# Encoder_Unit.net
KiCad netlist of a schematic drawn in Altium Designer
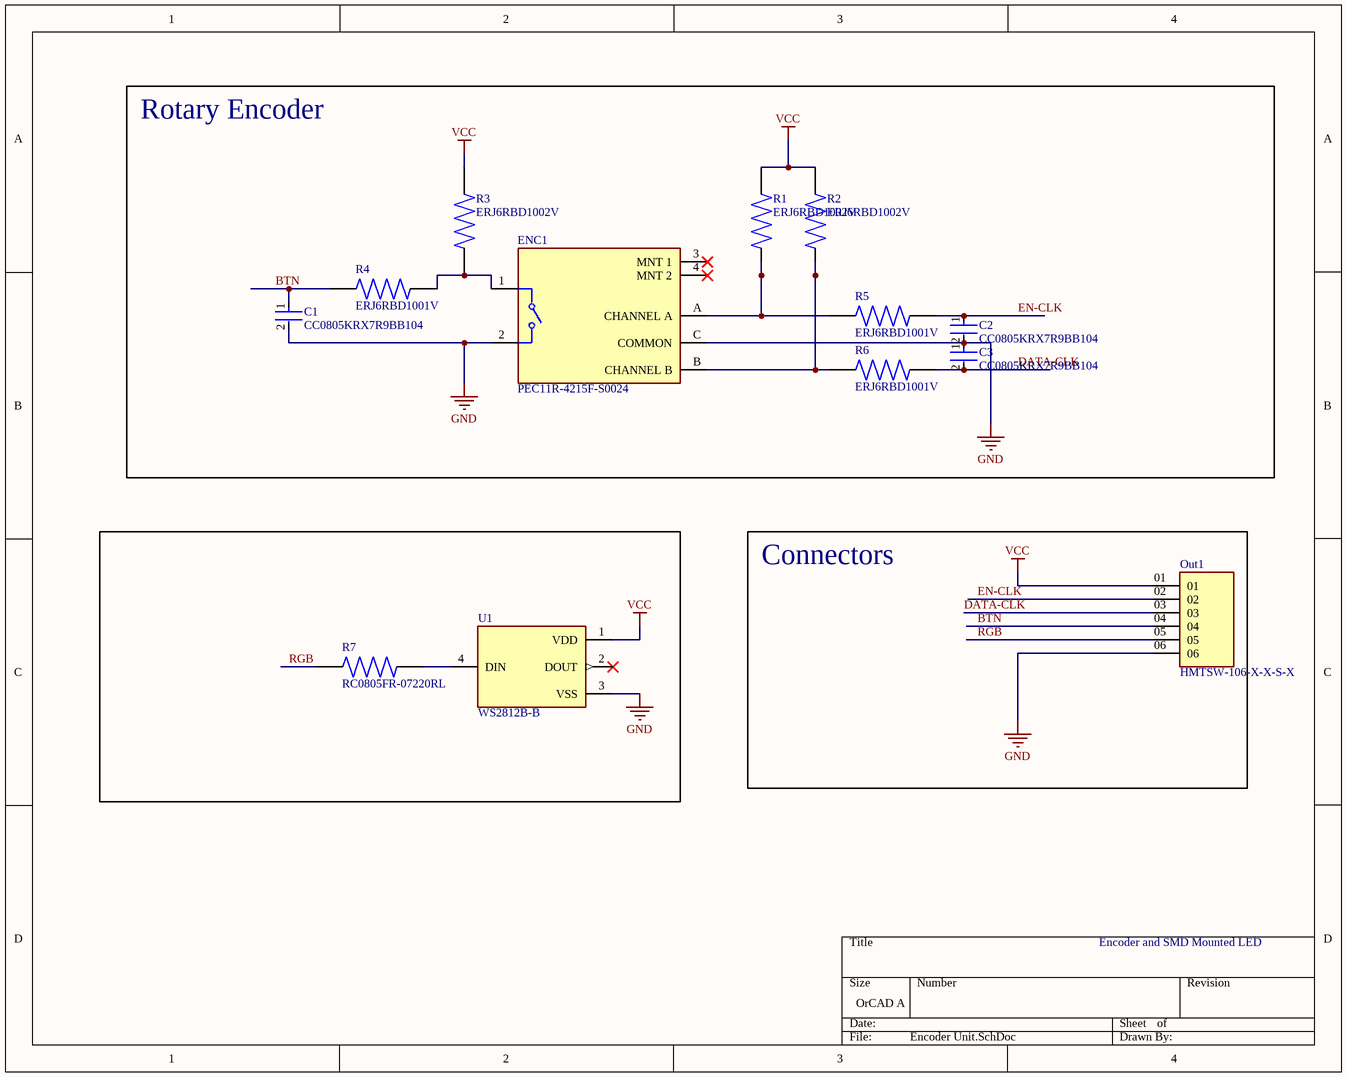
[diagram p0: Encoder Unit.SchDoc]

(export (version "E")
  (design (tool "Eeschema 10.0.6"))
  (components
    (comp (ref "C1")
      (value "CC0805KRX7R9BB104")
      (footprint "FP-CC0805-0_85-IPC_C")
      (description "CAP CER 0.1UF 50V X7R 0805")
      (fields (field (name "TOLERANCE") "0.1") (field (name "MANUFACTURER") "Yageo"))
      (libsource (lib "encoder_lcd_pcb") (part "CMP-2100-03606-3"))
    )
    (comp (ref "C2")
      (value "CC0805KRX7R9BB104")
      (footprint "FP-CC0805-0_85-IPC_C")
      (description "CAP CER 0.1UF 50V X7R 0805")
      (fields (field (name "TOLERANCE") "0.1") (field (name "MANUFACTURER") "Yageo"))
      (libsource (lib "encoder_lcd_pcb") (part "CMP-2100-03606-3"))
    )
    (comp (ref "C3")
      (value "CC0805KRX7R9BB104")
      (footprint "FP-CC0805-0_85-IPC_C")
      (description "CAP CER 0.1UF 50V X7R 0805")
      (fields (field (name "TOLERANCE") "0.1") (field (name "MANUFACTURER") "Yageo"))
      (libsource (lib "encoder_lcd_pcb") (part "CMP-2100-03606-3"))
    )
    (comp (ref "ENC1")
      (value "PEC11R-4215F-S0024")
      (footprint "FP-PEC11R-4215F-S0024-MFG")
      (description "ROTARY ENCODER MECHANICAL 24PPR")
      (fields (field (name "LCSC PART NUMBER") "C143790"))
      (libsource (lib "encoder_lcd_pcb") (part "CMP-1747-00012-2"))
    )
    (comp (ref "Out1")
      (value "HMTSW-106-X-X-S-X")
      (footprint "SAMTEC_HMTSW-106-X-X-S-X")
      (description ".100 High-Temp Variable Post Height Terminal Strip")
      (fields (field (name "MF") "SAMTEC") (field (name "MP") "HMTSW-106-07-T-S-200"))
      (libsource (lib "encoder_lcd_pcb") (part "HMTSW-106-X-X-S-X"))
    )
    (comp (ref "R1")
      (value "ERJ6RBD1002V")
      (footprint "RES_ERJ6RBD1002V")
      (fields (field (name "MF") "Panasonic"))
      (libsource (lib "encoder_lcd_pcb") (part "ERJ6RBD1002V"))
    )
    (comp (ref "R2")
      (value "ERJ6RBD1002V")
      (footprint "RES_ERJ6RBD1002V")
      (fields (field (name "MF") "Panasonic"))
      (libsource (lib "encoder_lcd_pcb") (part "ERJ6RBD1002V"))
    )
    (comp (ref "R3")
      (value "ERJ6RBD1002V")
      (footprint "RES_ERJ6RBD1002V")
      (fields (field (name "MF") "Panasonic"))
      (libsource (lib "encoder_lcd_pcb") (part "ERJ6RBD1002V"))
    )
    (comp (ref "R4")
      (value "ERJ6RBD1001V")
      (footprint "RES_ERJ6RBD1001V")
      (fields (field (name "MF") "Panasonic"))
      (libsource (lib "encoder_lcd_pcb") (part "ERJ6RBD1001V"))
    )
    (comp (ref "R5")
      (value "ERJ6RBD1001V")
      (footprint "RES_ERJ6RBD1001V")
      (fields (field (name "MF") "Panasonic"))
      (libsource (lib "encoder_lcd_pcb") (part "ERJ6RBD1001V"))
    )
    (comp (ref "R6")
      (value "ERJ6RBD1001V")
      (footprint "RES_ERJ6RBD1001V")
      (fields (field (name "MF") "Panasonic"))
      (libsource (lib "encoder_lcd_pcb") (part "ERJ6RBD1001V"))
    )
    (comp (ref "R7")
      (value "RC0805FR-07220RL")
      (footprint "RESC2012X60N")
      (description "220 Ohm Â±1% 0,125W, 1/8W Ã‡ip Direnci 0805 (2012 Metrik) Nem DirenÃ§li KalÄ±n Film")
      (fields (field (name "MF") "Yageo"))
      (libsource (lib "encoder_lcd_pcb") (part "RC0805FR-07220RL"))
    )
    (comp (ref "U1")
      (value "WS2812B-B")
      (footprint "encoder_lcd_pcb:LED_WS2812B-B")
      (description "Intelligent control LED integrated light source")
      (fields (field (name "LCSC PART NUMBER") "C114586"))
      (libsource (lib "encoder_lcd_pcb") (part "WS2812B-B"))
    )
  )
  (nets
    (net (code "1") (name "/BTN") (class "Default")
      (node (ref "C1") (pin "1") (pinfunction "1_1") (pintype "passive"))
      (node (ref "Out1") (pin "04") (pinfunction "04_04") (pintype "passive"))
      (node (ref "R4") (pin "1") (pinfunction "1_1") (pintype "passive"))
    )
    (net (code "2") (name "/DATA-CLK") (class "Default")
      (node (ref "C3") (pin "2") (pinfunction "2_2") (pintype "passive"))
      (node (ref "Out1") (pin "03") (pinfunction "03_03") (pintype "passive"))
      (node (ref "R6") (pin "2") (pinfunction "2_2") (pintype "passive"))
    )
    (net (code "3") (name "/EN-CLK") (class "Default")
      (node (ref "C2") (pin "1") (pinfunction "1_1") (pintype "passive"))
      (node (ref "Out1") (pin "02") (pinfunction "02_02") (pintype "passive"))
      (node (ref "R5") (pin "2") (pinfunction "2_2") (pintype "passive"))
    )
    (net (code "4") (name "/RGB") (class "Default")
      (node (ref "Out1") (pin "05") (pinfunction "05_05") (pintype "passive"))
      (node (ref "R7") (pin "1") (pinfunction "1_1") (pintype "passive"))
    )
    (net (code "5") (name "GND") (class "Default")
      (node (ref "C1") (pin "2") (pinfunction "2_2") (pintype "passive"))
      (node (ref "C2") (pin "2") (pinfunction "2_2") (pintype "passive"))
      (node (ref "C3") (pin "1") (pinfunction "1_1") (pintype "passive"))
      (node (ref "ENC1") (pin "2") (pinfunction "2_2") (pintype "passive"))
      (node (ref "ENC1") (pin "C") (pinfunction "COMMON_C") (pintype "passive"))
      (node (ref "Out1") (pin "06") (pinfunction "06_06") (pintype "passive"))
      (node (ref "U1") (pin "3") (pinfunction "VSS_3") (pintype "power_in"))
    )
    (net (code "6") (name "Net-(ENC1-CHANNEL_A)") (class "Default")
      (node (ref "ENC1") (pin "A") (pinfunction "CHANNEL_A_A") (pintype "passive"))
      (node (ref "R1") (pin "1") (pinfunction "1_1") (pintype "passive"))
      (node (ref "R5") (pin "1") (pinfunction "1_1") (pintype "passive"))
    )
    (net (code "7") (name "Net-(ENC1-CHANNEL_B)") (class "Default")
      (node (ref "ENC1") (pin "B") (pinfunction "CHANNEL_B_B") (pintype "passive"))
      (node (ref "R2") (pin "1") (pinfunction "1_1") (pintype "passive"))
      (node (ref "R6") (pin "1") (pinfunction "1_1") (pintype "passive"))
    )
    (net (code "8") (name "Net-(ENC1-Pad1)") (class "Default")
      (node (ref "ENC1") (pin "1") (pinfunction "1_1") (pintype "passive"))
      (node (ref "R3") (pin "1") (pinfunction "1_1") (pintype "passive"))
      (node (ref "R4") (pin "2") (pinfunction "2_2") (pintype "passive"))
    )
    (net (code "9") (name "Net-(U1-DIN)") (class "Default")
      (node (ref "R7") (pin "2") (pinfunction "2_2") (pintype "passive"))
      (node (ref "U1") (pin "4") (pinfunction "DIN_4") (pintype "passive"))
    )
    (net (code "10") (name "VCC") (class "Default")
      (node (ref "Out1") (pin "01") (pinfunction "01_01") (pintype "passive"))
      (node (ref "R1") (pin "2") (pinfunction "2_2") (pintype "passive"))
      (node (ref "R2") (pin "2") (pinfunction "2_2") (pintype "passive"))
      (node (ref "R3") (pin "2") (pinfunction "2_2") (pintype "passive"))
      (node (ref "U1") (pin "1") (pinfunction "VDD_1") (pintype "power_in"))
    )
    (net (code "11") (name "unconnected-(ENC1-MNT_1-Pad3)") (class "Default")
      (node (ref "ENC1") (pin "3") (pinfunction "MNT_1_3") (pintype "passive+no_connect"))
    )
    (net (code "12") (name "unconnected-(ENC1-MNT_2-Pad4)") (class "Default")
      (node (ref "ENC1") (pin "4") (pinfunction "MNT_2_4") (pintype "passive+no_connect"))
    )
    (net (code "13") (name "unconnected-(U1-DOUT-Pad2)") (class "Default")
      (node (ref "U1") (pin "2") (pinfunction "DOUT_2") (pintype "output+no_connect"))
    )
  )
)
